# touch_board.net
KiCad netlist of a schematic drawn in EAGLE
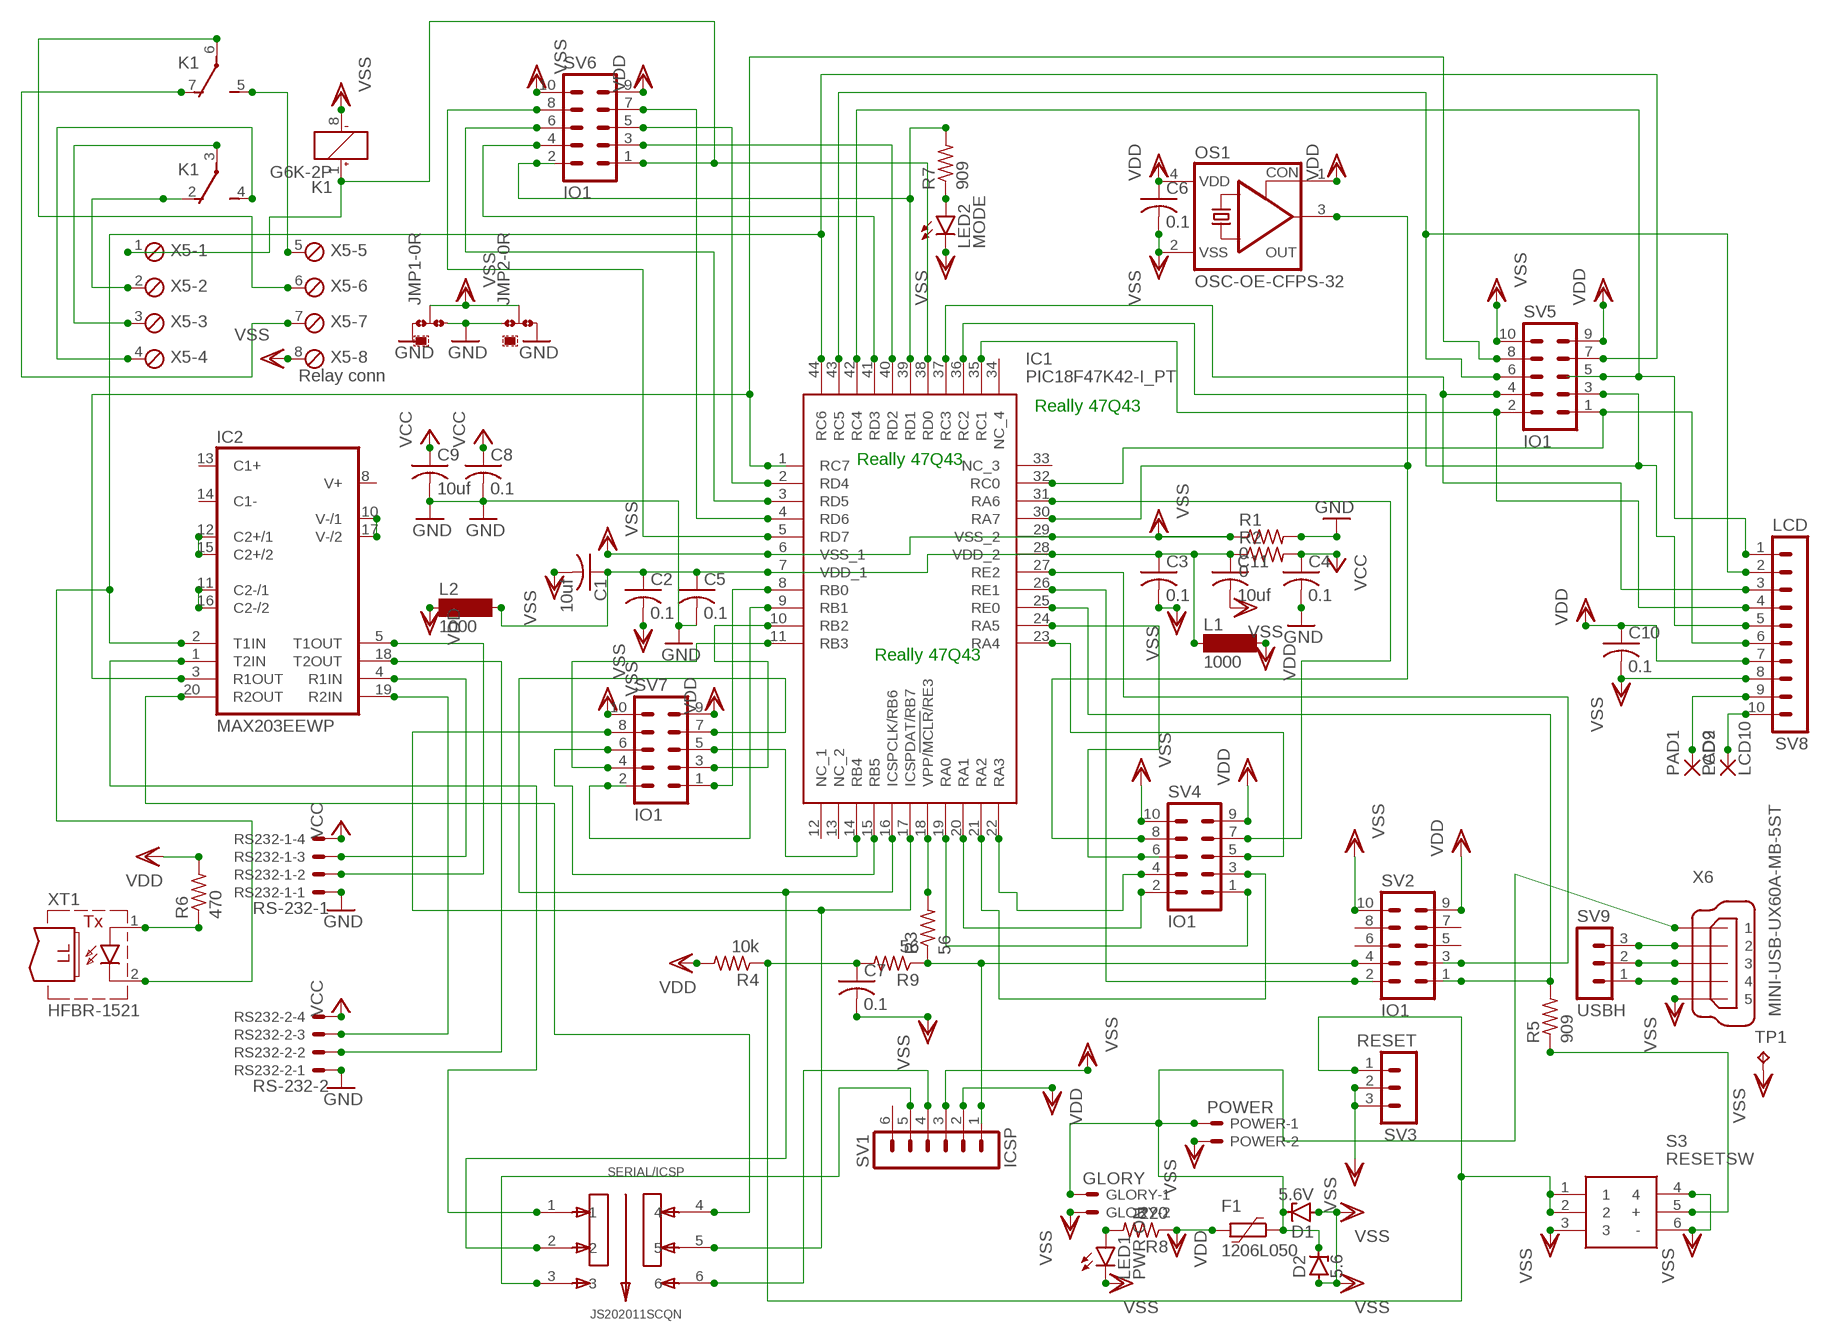
[diagram p0: schematic, sheet 1]

(export (version "E")
  (design (tool "Eeschema 10.0.6"))
  (components
    (comp (ref "C1")
      (value "10uf")
      (footprint "eagle-import:C0805")
      (libsource (lib "eagle-import") (part "C-USC0805"))
    )
    (comp (ref "C2")
      (value "0.1")
      (footprint "eagle-import:C0805")
      (libsource (lib "eagle-import") (part "C-USC0805"))
    )
    (comp (ref "C3")
      (value "0.1")
      (footprint "eagle-import:C0805")
      (libsource (lib "eagle-import") (part "C-USC0805"))
    )
    (comp (ref "C4")
      (value "0.1")
      (footprint "eagle-import:C0805")
      (libsource (lib "eagle-import") (part "C-USC0805"))
    )
    (comp (ref "C5")
      (value "0.1")
      (footprint "eagle-import:C0805")
      (libsource (lib "eagle-import") (part "C-USC0805"))
    )
    (comp (ref "C6")
      (value "0.1")
      (footprint "eagle-import:C0805")
      (libsource (lib "eagle-import") (part "C-USC0805"))
    )
    (comp (ref "C7")
      (value "0.1")
      (footprint "eagle-import:C0805")
      (libsource (lib "eagle-import") (part "C-USC0805"))
    )
    (comp (ref "C8")
      (value "0.1")
      (footprint "eagle-import:C0805")
      (libsource (lib "eagle-import") (part "C-USC0805"))
    )
    (comp (ref "C9")
      (value "10uf")
      (footprint "eagle-import:C0805")
      (libsource (lib "eagle-import") (part "C-USC0805"))
    )
    (comp (ref "C10")
      (value "0.1")
      (footprint "eagle-import:C0805")
      (libsource (lib "eagle-import") (part "C-USC0805"))
    )
    (comp (ref "C11")
      (value "10uf")
      (footprint "eagle-import:C0805")
      (libsource (lib "eagle-import") (part "C-USC0805"))
    )
    (comp (ref "D1")
      (value "5.6V")
      (footprint "eagle-import:ZDIO-7.5")
      (libsource (lib "eagle-import") (part "ZENER-DIODEZD-7.5"))
    )
    (comp (ref "D2")
      (value "5.6")
      (footprint "eagle-import:SMB")
      (libsource (lib "eagle-import") (part "ZENER-DIODESMB"))
    )
    (comp (ref "F1")
      (value "1206L050")
      (footprint "eagle-import:1206L")
      (fields (field (name "MF") "Littelfuse"))
      (libsource (lib "eagle-import") (part "?1206L050"))
    )
    (comp (ref "GLORY")
      (value "GLORY")
      (footprint "eagle-import:22-23-2021")
      (fields (field (name "MF") "MOLEX") (field (name "MPN") "22-23-2021"))
      (libsource (lib "eagle-import") (part "22-23-2021"))
    )
    (comp (ref "IC1")
      (value "PIC18F47K42-I_PT")
      (footprint "eagle-import:QFP80P1200X1200X120-44N")
      (fields
        (field (name "MANUFACTURER_PART_NUMBER") "PIC18F47K42-I/PT")
        (field (name "MOUSER_PART_NUMBER") "579-PIC18F47K42-I/PT")
      )
      (libsource (lib "eagle-import") (part "PIC18F47K42-I_PT"))
    )
    (comp (ref "IC2")
      (value "MAX203EEWP")
      (footprint "eagle-import:SO20L")
      (libsource (lib "eagle-import") (part "MAX203WPEE"))
    )
    (comp (ref "JMP1")
      (value "0R-JUMPA")
      (footprint "eagle-import:A0R-JMP")
      (libsource (lib "eagle-import") (part "0R-JUMPA"))
    )
    (comp (ref "JMP2")
      (value "0R-JUMPA")
      (footprint "eagle-import:A0R-JMP")
      (libsource (lib "eagle-import") (part "0R-JUMPA"))
    )
    (comp (ref "K1")
      (value "G6K-2P")
      (footprint "eagle-import:G6K-2P")
      (fields (field (name "MF") "OMRON COMPONENTS USA") (field (name "MPN") "G6K-2P DC3"))
      (libsource (lib "eagle-import") (part "G6K-2P"))
    )
    (comp (ref "L1")
      (value "1000")
      (footprint "eagle-import:SM-1206")
      (libsource (lib "eagle-import") (part "SM-1206"))
    )
    (comp (ref "L2")
      (value "1000")
      (footprint "eagle-import:SM-1206")
      (libsource (lib "eagle-import") (part "SM-1206"))
    )
    (comp (ref "LED1")
      (value "PWR ON")
      (footprint "eagle-import:CHIPLED_1206")
      (libsource (lib "eagle-import") (part "LEDCHIPLED_1206"))
    )
    (comp (ref "LED2")
      (value "MODE")
      (footprint "eagle-import:CHIPLED_1206")
      (libsource (lib "eagle-import") (part "LEDCHIPLED_1206"))
    )
    (comp (ref "OS1")
      (value "OSC-OE-CFPS-32")
      (footprint "eagle-import:7.2X5.2-4-PAD")
      (libsource (lib "eagle-import") (part "OSC-OE-CFPS-32"))
    )
    (comp (ref "PAD1")
      (value "LCD9")
      (footprint "eagle-import:SMD1,27-2,54")
      (libsource (lib "eagle-import") (part "SMD2"))
    )
    (comp (ref "PAD2")
      (value "LCD10")
      (footprint "eagle-import:SMD1,27-2,54")
      (libsource (lib "eagle-import") (part "SMD2"))
    )
    (comp (ref "POWER")
      (value "POWER")
      (footprint "eagle-import:22-23-2021")
      (fields (field (name "MF") "MOLEX") (field (name "MPN") "22-23-2021"))
      (libsource (lib "eagle-import") (part "22-23-2021"))
    )
    (comp (ref "R1")
      (value "0")
      (footprint "eagle-import:R0805")
      (libsource (lib "eagle-import") (part "R-US_R0805"))
    )
    (comp (ref "R2")
      (value "0")
      (footprint "eagle-import:R0805")
      (libsource (lib "eagle-import") (part "R-US_R0805"))
    )
    (comp (ref "R3")
      (value "56")
      (footprint "eagle-import:R0805")
      (libsource (lib "eagle-import") (part "R-US_R0805"))
    )
    (comp (ref "R4")
      (value "10k")
      (footprint "eagle-import:R0805")
      (libsource (lib "eagle-import") (part "R-US_R0805"))
    )
    (comp (ref "R5")
      (value "909")
      (footprint "eagle-import:R0805")
      (libsource (lib "eagle-import") (part "R-US_R0805"))
    )
    (comp (ref "R6")
      (value "470")
      (footprint "eagle-import:R0805")
      (libsource (lib "eagle-import") (part "R-US_R0805"))
    )
    (comp (ref "R7")
      (value "909")
      (footprint "eagle-import:R0805")
      (libsource (lib "eagle-import") (part "R-US_R0805"))
    )
    (comp (ref "R8")
      (value "220")
      (footprint "eagle-import:R0805")
      (libsource (lib "eagle-import") (part "R-US_R0805"))
    )
    (comp (ref "R9")
      (value "56")
      (footprint "eagle-import:R0805")
      (libsource (lib "eagle-import") (part "R-US_R0805"))
    )
    (comp (ref "RS232-1")
      (value "RS-232-1")
      (footprint "eagle-import:22-23-2041")
      (fields (field (name "MF") "MOLEX") (field (name "MPN") "22-23-2041"))
      (libsource (lib "eagle-import") (part "22-23-2041"))
    )
    (comp (ref "RS232-2")
      (value "RS-232-2")
      (footprint "eagle-import:22-23-2041")
      (fields (field (name "MF") "MOLEX") (field (name "MPN") "22-23-2041"))
      (libsource (lib "eagle-import") (part "22-23-2041"))
    )
    (comp (ref "S3")
      (value "RESETSW")
      (footprint "eagle-import:B3W-9_1-LED")
      (fields
        (field (name "MANUFACTURER_PART_NUMBER") "B3W-9000-Y1N")
        (field (name "MOUSER_PART_NUMBER") "653-B3W-9000-Y1N")
        (field (name "RS_PART_NUMBER") "0492777P")
      )
      (libsource (lib "eagle-import") (part "B3W-9000-Y1N"))
    )
    (comp (ref "SERIAL/ICSP")
      (value "JS202011SCQN")
      (footprint "eagle-import:SW_JS202011SCQN")
      (fields (field (name "MF") "C&K"))
      (libsource (lib "eagle-import") (part "JS202011SCQN"))
    )
    (comp (ref "SV1")
      (value "ICSP")
      (footprint "eagle-import:MA06-1")
      (libsource (lib "eagle-import") (part "MA06-1"))
    )
    (comp (ref "SV2")
      (value "IO1")
      (footprint "eagle-import:MA05-2")
      (libsource (lib "eagle-import") (part "MA05-2"))
    )
    (comp (ref "SV3")
      (value "RESET")
      (footprint "eagle-import:MA03-1")
      (libsource (lib "eagle-import") (part "MA03-1"))
    )
    (comp (ref "SV4")
      (value "IO1")
      (footprint "eagle-import:MA05-2")
      (libsource (lib "eagle-import") (part "MA05-2"))
    )
    (comp (ref "SV5")
      (value "IO1")
      (footprint "eagle-import:MA05-2")
      (libsource (lib "eagle-import") (part "MA05-2"))
    )
    (comp (ref "SV6")
      (value "IO1")
      (footprint "eagle-import:MA05-2")
      (libsource (lib "eagle-import") (part "MA05-2"))
    )
    (comp (ref "SV7")
      (value "IO1")
      (footprint "eagle-import:MA05-2")
      (libsource (lib "eagle-import") (part "MA05-2"))
    )
    (comp (ref "SV8")
      (value "LCD")
      (footprint "eagle-import:MA10-1")
      (libsource (lib "eagle-import") (part "MA10-1"))
    )
    (comp (ref "SV9")
      (value "USBH")
      (footprint "eagle-import:MA03-1")
      (libsource (lib "eagle-import") (part "MA03-1"))
    )
    (comp (ref "TP1")
      (value "TPB1,27")
      (footprint "eagle-import:B1,27")
      (libsource (lib "eagle-import") (part "TPB1,27"))
    )
    (comp (ref "X5")
      (value "Relay conn")
      (footprint "eagle-import:8POL254")
      (libsource (lib "eagle-import") (part "MPT8"))
    )
    (comp (ref "X6")
      (value "MINI-USB-UX60A-MB-5ST")
      (footprint "eagle-import:UX60A-MB-5ST")
      (libsource (lib "eagle-import") (part "MINI-USB-UX60A-MB-5ST"))
    )
    (comp (ref "XT1")
      (value "HFBR-1521")
      (footprint "eagle-import:HFBR-15X3")
      (fields (field (name "MF") "AGILENT TECHNOLOGIES"))
      (libsource (lib "eagle-import") (part "HFBR-1521"))
    )
  )
  (nets
    (net (code "1") (name "GND") (class "Default")
      (node (ref "C4") (pin "2") (pinfunction "2_2") (pintype "passive"))
      (node (ref "C5") (pin "2") (pinfunction "2_2") (pintype "passive"))
      (node (ref "C8") (pin "2") (pinfunction "2_2") (pintype "passive"))
      (node (ref "C9") (pin "2") (pinfunction "2_2") (pintype "passive"))
      (node (ref "JMP1") (pin "1") (pinfunction "1_1") (pintype "passive"))
      (node (ref "JMP1") (pin "3") (pinfunction "3_3") (pintype "passive"))
      (node (ref "JMP2") (pin "1") (pinfunction "1_1") (pintype "passive"))
      (node (ref "JMP2") (pin "3") (pinfunction "3_3") (pintype "passive"))
      (node (ref "R1") (pin "2") (pinfunction "2_2") (pintype "passive"))
      (node (ref "RS232-1") (pin "1") (pinfunction "S_1") (pintype "passive"))
      (node (ref "RS232-2") (pin "1") (pinfunction "S_1") (pintype "passive"))
    )
    (net (code "2") (name "Net-(C7-Pad1)") (class "Default")
      (node (ref "C7") (pin "1") (pinfunction "1_1") (pintype "passive"))
      (node (ref "R4") (pin "1") (pinfunction "1_1") (pintype "passive"))
      (node (ref "R9") (pin "2") (pinfunction "2_2") (pintype "passive"))
      (node (ref "S3") (pin "1") (pinfunction "1_1") (pintype "bidirectional"))
      (node (ref "S3") (pin "2") (pinfunction "2_2") (pintype "bidirectional"))
      (node (ref "SV3") (pin "1") (pinfunction "1_1") (pintype "passive"))
    )
    (net (code "3") (name "Net-(GLORYA-S)") (class "Default")
      (node (ref "D1") (pin "C") (pinfunction "C_C") (pintype "passive"))
      (node (ref "D2") (pin "C") (pinfunction "C_C") (pintype "passive"))
      (node (ref "F1") (pin "1") (pinfunction "1_1") (pintype "passive"))
      (node (ref "GLORY") (pin "1") (pinfunction "S_1") (pintype "passive"))
      (node (ref "POWER") (pin "1") (pinfunction "S_1") (pintype "passive"))
      (node (ref "X6") (pin "1") (pinfunction "1_1") (pintype "input"))
    )
    (net (code "4") (name "Net-(IC1-ICSPCLK{slash}RB6)") (class "Default")
      (node (ref "IC1") (pin "16") (pinfunction "ICSPCLK/RB6_16") (pintype "bidirectional"))
      (node (ref "SERIAL/ICSP") (pin "2") (pinfunction "2_2") (pintype "passive"))
      (node (ref "SV7") (pin "7") (pinfunction "7_7") (pintype "passive"))
    )
    (net (code "5") (name "Net-(IC1-ICSPDAT{slash}RB7)") (class "Default")
      (node (ref "IC1") (pin "17") (pinfunction "ICSPDAT/RB7_17") (pintype "bidirectional"))
      (node (ref "SERIAL/ICSP") (pin "5") (pinfunction "5_5") (pintype "passive"))
      (node (ref "SV7") (pin "8") (pinfunction "8_8") (pintype "passive"))
    )
    (net (code "6") (name "Net-(IC1-RA0)") (class "Default")
      (node (ref "IC1") (pin "19") (pinfunction "RA0_19") (pintype "bidirectional"))
      (node (ref "SV4") (pin "1") (pinfunction "1_1") (pintype "passive"))
    )
    (net (code "7") (name "Net-(IC1-RA1)") (class "Default")
      (node (ref "IC1") (pin "20") (pinfunction "RA1_20") (pintype "bidirectional"))
      (node (ref "SV4") (pin "2") (pinfunction "2_2") (pintype "passive"))
    )
    (net (code "8") (name "Net-(IC1-RA2)") (class "Default")
      (node (ref "IC1") (pin "21") (pinfunction "RA2_21") (pintype "bidirectional"))
      (node (ref "SV4") (pin "3") (pinfunction "3_3") (pintype "passive"))
    )
    (net (code "9") (name "Net-(IC1-RA3)") (class "Default")
      (node (ref "IC1") (pin "22") (pinfunction "RA3_22") (pintype "bidirectional"))
      (node (ref "SV4") (pin "4") (pinfunction "4_4") (pintype "passive"))
    )
    (net (code "10") (name "Net-(IC1-RA4)") (class "Default")
      (node (ref "IC1") (pin "23") (pinfunction "RA4_23") (pintype "bidirectional"))
      (node (ref "SV4") (pin "5") (pinfunction "5_5") (pintype "passive"))
    )
    (net (code "11") (name "Net-(IC1-RA5)") (class "Default")
      (node (ref "IC1") (pin "24") (pinfunction "RA5_24") (pintype "bidirectional"))
      (node (ref "SV4") (pin "6") (pinfunction "6_6") (pintype "passive"))
    )
    (net (code "12") (name "Net-(IC1-RA6)") (class "Default")
      (node (ref "IC1") (pin "31") (pinfunction "RA6_31") (pintype "bidirectional"))
      (node (ref "SV4") (pin "7") (pinfunction "7_7") (pintype "passive"))
    )
    (net (code "13") (name "Net-(IC1-RA7)") (class "Default")
      (node (ref "IC1") (pin "30") (pinfunction "RA7_30") (pintype "bidirectional"))
      (node (ref "OS1") (pin "3") (pinfunction "OUT_3") (pintype "output"))
      (node (ref "SV4") (pin "8") (pinfunction "8_8") (pintype "passive"))
    )
    (net (code "14") (name "Net-(IC1-RB0)") (class "Default")
      (node (ref "IC1") (pin "8") (pinfunction "RB0_8") (pintype "bidirectional"))
      (node (ref "SV7") (pin "1") (pinfunction "1_1") (pintype "passive"))
    )
    (net (code "15") (name "Net-(IC1-RB1)") (class "Default")
      (node (ref "IC1") (pin "9") (pinfunction "RB1_9") (pintype "bidirectional"))
      (node (ref "SV7") (pin "2") (pinfunction "2_2") (pintype "passive"))
    )
    (net (code "16") (name "Net-(IC1-RB2)") (class "Default")
      (node (ref "IC1") (pin "10") (pinfunction "RB2_10") (pintype "bidirectional"))
      (node (ref "SV7") (pin "3") (pinfunction "3_3") (pintype "passive"))
    )
    (net (code "17") (name "Net-(IC1-RB3)") (class "Default")
      (node (ref "IC1") (pin "11") (pinfunction "RB3_11") (pintype "bidirectional"))
      (node (ref "SV7") (pin "4") (pinfunction "4_4") (pintype "passive"))
    )
    (net (code "18") (name "Net-(IC1-RB4)") (class "Default")
      (node (ref "IC1") (pin "14") (pinfunction "RB4_14") (pintype "bidirectional"))
      (node (ref "SV7") (pin "5") (pinfunction "5_5") (pintype "passive"))
    )
    (net (code "19") (name "Net-(IC1-RB5)") (class "Default")
      (node (ref "IC1") (pin "15") (pinfunction "RB5_15") (pintype "bidirectional"))
      (node (ref "SV7") (pin "6") (pinfunction "6_6") (pintype "passive"))
    )
    (net (code "20") (name "Net-(IC1-RC0)") (class "Default")
      (node (ref "IC1") (pin "32") (pinfunction "RC0_32") (pintype "bidirectional"))
      (node (ref "SV5") (pin "1") (pinfunction "1_1") (pintype "passive"))
      (node (ref "SV8") (pin "6") (pinfunction "6_6") (pintype "passive"))
    )
    (net (code "21") (name "Net-(IC1-RC1)") (class "Default")
      (node (ref "IC1") (pin "35") (pinfunction "RC1_35") (pintype "bidirectional"))
      (node (ref "SV5") (pin "2") (pinfunction "2_2") (pintype "passive"))
      (node (ref "SV8") (pin "4") (pinfunction "4_4") (pintype "passive"))
    )
    (net (code "22") (name "Net-(IC1-RC2)") (class "Default")
      (node (ref "IC1") (pin "36") (pinfunction "RC2_36") (pintype "bidirectional"))
      (node (ref "SV5") (pin "3") (pinfunction "3_3") (pintype "passive"))
      (node (ref "SV8") (pin "5") (pinfunction "5_5") (pintype "passive"))
    )
    (net (code "23") (name "Net-(IC1-RC3)") (class "Default")
      (node (ref "IC1") (pin "37") (pinfunction "RC3_37") (pintype "bidirectional"))
      (node (ref "SV5") (pin "4") (pinfunction "4_4") (pintype "passive"))
      (node (ref "SV8") (pin "3") (pinfunction "3_3") (pintype "passive"))
    )
    (net (code "24") (name "Net-(IC1-RC4)") (class "Default")
      (node (ref "IC1") (pin "42") (pinfunction "RC4_42") (pintype "bidirectional"))
      (node (ref "SV5") (pin "5") (pinfunction "5_5") (pintype "passive"))
      (node (ref "SV8") (pin "1") (pinfunction "1_1") (pintype "passive"))
    )
    (net (code "25") (name "Net-(IC1-RC5)") (class "Default")
      (node (ref "IC1") (pin "43") (pinfunction "RC5_43") (pintype "bidirectional"))
      (node (ref "SV5") (pin "6") (pinfunction "6_6") (pintype "passive"))
      (node (ref "SV8") (pin "2") (pinfunction "2_2") (pintype "passive"))
    )
    (net (code "26") (name "Net-(IC1-RC6)") (class "Default")
      (node (ref "IC1") (pin "44") (pinfunction "RC6_44") (pintype "bidirectional"))
      (node (ref "IC2") (pin "2") (pinfunction "T1IN_2") (pintype "input"))
      (node (ref "SV5") (pin "7") (pinfunction "7_7") (pintype "passive"))
      (node (ref "XT1") (pin "2") (pinfunction "C_2") (pintype "passive"))
    )
    (net (code "27") (name "Net-(IC1-RC7)") (class "Default")
      (node (ref "IC1") (pin "1") (pinfunction "RC7_1") (pintype "bidirectional"))
      (node (ref "IC2") (pin "3") (pinfunction "R1OUT_3") (pintype "output"))
      (node (ref "SV5") (pin "8") (pinfunction "8_8") (pintype "passive"))
    )
    (net (code "28") (name "Net-(IC1-RD0)") (class "Default")
      (node (ref "IC1") (pin "38") (pinfunction "RD0_38") (pintype "bidirectional"))
      (node (ref "K1") (pin "1") (pinfunction "+_1") (pintype "passive"))
      (node (ref "SV6") (pin "1") (pinfunction "1_1") (pintype "passive"))
      (node (ref "X5") (pin "1") (pinfunction "1_1") (pintype "passive"))
    )
    (net (code "29") (name "Net-(IC1-RD1)") (class "Default")
      (node (ref "IC1") (pin "39") (pinfunction "RD1_39") (pintype "bidirectional"))
      (node (ref "R7") (pin "2") (pinfunction "2_2") (pintype "passive"))
      (node (ref "SV6") (pin "2") (pinfunction "2_2") (pintype "passive"))
    )
    (net (code "30") (name "Net-(IC1-RD2)") (class "Default")
      (node (ref "IC1") (pin "40") (pinfunction "RD2_40") (pintype "bidirectional"))
      (node (ref "SV6") (pin "3") (pinfunction "3_3") (pintype "passive"))
    )
    (net (code "31") (name "Net-(IC1-RD3)") (class "Default")
      (node (ref "IC1") (pin "41") (pinfunction "RD3_41") (pintype "bidirectional"))
      (node (ref "SV6") (pin "4") (pinfunction "4_4") (pintype "passive"))
    )
    (net (code "32") (name "Net-(IC1-RD4)") (class "Default")
      (node (ref "IC1") (pin "2") (pinfunction "RD4_2") (pintype "bidirectional"))
      (node (ref "SV6") (pin "5") (pinfunction "5_5") (pintype "passive"))
    )
    (net (code "33") (name "Net-(IC1-RD5)") (class "Default")
      (node (ref "IC1") (pin "3") (pinfunction "RD5_3") (pintype "bidirectional"))
      (node (ref "SV6") (pin "6") (pinfunction "6_6") (pintype "passive"))
    )
    (net (code "34") (name "Net-(IC1-RD6)") (class "Default")
      (node (ref "IC1") (pin "4") (pinfunction "RD6_4") (pintype "bidirectional"))
      (node (ref "SV6") (pin "7") (pinfunction "7_7") (pintype "passive"))
    )
    (net (code "35") (name "Net-(IC1-RD7)") (class "Default")
      (node (ref "IC1") (pin "5") (pinfunction "RD7_5") (pintype "bidirectional"))
      (node (ref "SV6") (pin "8") (pinfunction "8_8") (pintype "passive"))
    )
    (net (code "36") (name "Net-(IC1-RE0)") (class "Default")
      (node (ref "IC1") (pin "25") (pinfunction "RE0_25") (pintype "bidirectional"))
      (node (ref "R5") (pin "2") (pinfunction "2_2") (pintype "passive"))
      (node (ref "SV2") (pin "1") (pinfunction "1_1") (pintype "passive"))
    )
    (net (code "37") (name "Net-(IC1-RE1)") (class "Default")
      (node (ref "IC1") (pin "26") (pinfunction "RE1_26") (pintype "bidirectional"))
      (node (ref "SV2") (pin "2") (pinfunction "2_2") (pintype "passive"))
    )
    (net (code "38") (name "Net-(IC1-RE2)") (class "Default")
      (node (ref "IC1") (pin "27") (pinfunction "RE2_27") (pintype "bidirectional"))
      (node (ref "SV2") (pin "3") (pinfunction "3_3") (pintype "passive"))
    )
    (net (code "39") (name "Net-(IC1-VDD_1)") (class "Default")
      (node (ref "C1") (pin "1") (pinfunction "1_1") (pintype "passive"))
      (node (ref "C11") (pin "1") (pinfunction "1_1") (pintype "passive"))
      (node (ref "C2") (pin "1") (pinfunction "1_1") (pintype "passive"))
      (node (ref "C3") (pin "1") (pinfunction "1_1") (pintype "passive"))
      (node (ref "C5") (pin "1") (pinfunction "1_1") (pintype "passive"))
      (node (ref "IC1") (pin "28") (pinfunction "VDD_2_28") (pintype "bidirectional"))
      (node (ref "IC1") (pin "7") (pinfunction "VDD_1_7") (pintype "bidirectional"))
      (node (ref "L1") (pin "1") (pinfunction "1_1") (pintype "passive"))
      (node (ref "L2") (pin "2") (pinfunction "2_2") (pintype "passive"))
      (node (ref "R2") (pin "1") (pinfunction "1_1") (pintype "passive"))
    )
    (net (code "40") (name "Net-(IC1-VPP{slash}~{MCLR}{slash}RE3)") (class "Default")
      (node (ref "IC1") (pin "18") (pinfunction "VPP/~{MCLR}/RE3_18") (pintype "bidirectional"))
      (node (ref "R3") (pin "2") (pinfunction "2_2") (pintype "passive"))
    )
    (net (code "41") (name "Net-(IC2A-C2+{slash}1)") (class "Default")
      (node (ref "IC2") (pin "12") (pinfunction "C2+/1_12") (pintype "passive"))
      (node (ref "IC2") (pin "15") (pinfunction "C2+/2_15") (pintype "passive"))
    )
    (net (code "42") (name "Net-(IC2A-C2-{slash}1)") (class "Default")
      (node (ref "IC2") (pin "11") (pinfunction "C2-/1_11") (pintype "passive"))
      (node (ref "IC2") (pin "16") (pinfunction "C2-/2_16") (pintype "passive"))
    )
    (net (code "43") (name "Net-(IC2A-R1IN)") (class "Default")
      (node (ref "IC2") (pin "4") (pinfunction "R1IN_4") (pintype "input"))
      (node (ref "RS232-1") (pin "3") (pinfunction "S_3") (pintype "passive"))
    )
    (net (code "44") (name "Net-(IC2A-R2IN)") (class "Default")
      (node (ref "IC2") (pin "19") (pinfunction "R2IN_19") (pintype "input"))
      (node (ref "RS232-2") (pin "3") (pinfunction "S_3") (pintype "passive"))
    )
    (net (code "45") (name "Net-(IC2A-R2OUT)") (class "Default")
      (node (ref "IC2") (pin "20") (pinfunction "R2OUT_20") (pintype "output"))
      (node (ref "SERIAL/ICSP") (pin "4") (pinfunction "4_4") (pintype "passive"))
    )
    (net (code "46") (name "Net-(IC2A-T1OUT)") (class "Default")
      (node (ref "IC2") (pin "5") (pinfunction "T1OUT_5") (pintype "output"))
      (node (ref "RS232-1") (pin "2") (pinfunction "S_2") (pintype "passive"))
    )
    (net (code "47") (name "Net-(IC2A-T2IN)") (class "Default")
      (node (ref "IC2") (pin "1") (pinfunction "T2IN_1") (pintype "input"))
      (node (ref "SERIAL/ICSP") (pin "1") (pinfunction "1_1") (pintype "passive"))
    )
    (net (code "48") (name "Net-(IC2A-T2OUT)") (class "Default")
      (node (ref "IC2") (pin "18") (pinfunction "T2OUT_18") (pintype "output"))
      (node (ref "RS232-2") (pin "2") (pinfunction "S_2") (pintype "passive"))
    )
    (net (code "49") (name "Net-(IC2A-V-{slash}1)") (class "Default")
      (node (ref "IC2") (pin "10") (pinfunction "V-/1_10") (pintype "passive"))
      (node (ref "IC2") (pin "17") (pinfunction "V-/2_17") (pintype "passive"))
    )
    (net (code "50") (name "Net-(K1B-O)") (class "Default")
      (node (ref "K1") (pin "2") (pinfunction "O_2") (pintype "passive"))
      (node (ref "X5") (pin "2") (pinfunction "1_2") (pintype "passive"))
    )
    (net (code "51") (name "Net-(K1B-P)") (class "Default")
      (node (ref "K1") (pin "3") (pinfunction "P_3") (pintype "passive"))
      (node (ref "X5") (pin "3") (pinfunction "1_3") (pintype "passive"))
    )
    (net (code "52") (name "Net-(K1B-S)") (class "Default")
      (node (ref "K1") (pin "4") (pinfunction "S_4") (pintype "passive"))
      (node (ref "X5") (pin "4") (pinfunction "1_4") (pintype "passive"))
    )
    (net (code "53") (name "Net-(K1C-O)") (class "Default")
      (node (ref "K1") (pin "7") (pinfunction "O_7") (pintype "passive"))
      (node (ref "X5") (pin "7") (pinfunction "1_7") (pintype "passive"))
    )
    (net (code "54") (name "Net-(K1C-P)") (class "Default")
      (node (ref "K1") (pin "6") (pinfunction "P_6") (pintype "passive"))
      (node (ref "X5") (pin "6") (pinfunction "1_6") (pintype "passive"))
    )
    (net (code "55") (name "Net-(K1C-S)") (class "Default")
      (node (ref "K1") (pin "5") (pinfunction "S_5") (pintype "passive"))
      (node (ref "X5") (pin "5") (pinfunction "1_5") (pintype "passive"))
    )
    (net (code "56") (name "Net-(LED1-PadA)") (class "Default")
      (node (ref "LED1") (pin "A") (pinfunction "A_A") (pintype "passive"))
      (node (ref "R8") (pin "2") (pinfunction "2_2") (pintype "passive"))
    )
    (net (code "57") (name "Net-(LED2-PadA)") (class "Default")
      (node (ref "LED2") (pin "A") (pinfunction "A_A") (pintype "passive"))
      (node (ref "R7") (pin "1") (pinfunction "1_1") (pintype "passive"))
    )
    (net (code "58") (name "Net-(PAD1-P)") (class "Default")
      (node (ref "PAD1") (pin "1") (pinfunction "P_1") (pintype "passive"))
      (node (ref "SV8") (pin "9") (pinfunction "9_9") (pintype "passive"))
    )
    (net (code "59") (name "Net-(PAD2-P)") (class "Default")
      (node (ref "PAD2") (pin "1") (pinfunction "P_1") (pintype "passive"))
      (node (ref "SV8") (pin "10") (pinfunction "10_10") (pintype "passive"))
    )
    (net (code "60") (name "Net-(R3-Pad1)") (class "Default")
      (node (ref "R3") (pin "1") (pinfunction "1_1") (pintype "passive"))
      (node (ref "R9") (pin "1") (pinfunction "1_1") (pintype "passive"))
      (node (ref "SV1") (pin "1") (pinfunction "1_1") (pintype "passive"))
      (node (ref "SV2") (pin "4") (pinfunction "4_4") (pintype "passive"))
    )
    (net (code "61") (name "Net-(S3-+)") (class "Default")
      (node (ref "R5") (pin "1") (pinfunction "1_1") (pintype "passive"))
      (node (ref "S3") (pin "5") (pinfunction "+_5") (pintype "bidirectional"))
    )
    (net (code "62") (name "Net-(SERIAL/ICSP-Pad3)") (class "Default")
      (node (ref "SERIAL/ICSP") (pin "3") (pinfunction "3_3") (pintype "passive"))
      (node (ref "SV1") (pin "5") (pinfunction "5_5") (pintype "passive"))
    )
    (net (code "63") (name "Net-(SERIAL/ICSP-Pad6)") (class "Default")
      (node (ref "SERIAL/ICSP") (pin "6") (pinfunction "6_6") (pintype "passive"))
      (node (ref "SV1") (pin "4") (pinfunction "4_4") (pintype "passive"))
    )
    (net (code "64") (name "Net-(SV9-Pad1)") (class "Default")
      (node (ref "SV9") (pin "1") (pinfunction "1_1") (pintype "passive"))
      (node (ref "X6") (pin "4") (pinfunction "4_4") (pintype "input"))
    )
    (net (code "65") (name "Net-(SV9-Pad2)") (class "Default")
      (node (ref "SV9") (pin "2") (pinfunction "2_2") (pintype "passive"))
      (node (ref "X6") (pin "3") (pinfunction "3_3") (pintype "input"))
    )
    (net (code "66") (name "Net-(SV9-Pad3)") (class "Default")
      (node (ref "SV9") (pin "3") (pinfunction "3_3") (pintype "passive"))
      (node (ref "X6") (pin "2") (pinfunction "2_2") (pintype "input"))
    )
    (net (code "67") (name "Net-(XT1-A)") (class "Default")
      (node (ref "R6") (pin "1") (pinfunction "1_1") (pintype "passive"))
      (node (ref "XT1") (pin "1") (pinfunction "A_1") (pintype "passive"))
    )
    (net (code "68") (name "VCC") (class "Default")
      (node (ref "C4") (pin "1") (pinfunction "1_1") (pintype "passive"))
      (node (ref "C8") (pin "1") (pinfunction "1_1") (pintype "passive"))
      (node (ref "C9") (pin "1") (pinfunction "1_1") (pintype "passive"))
      (node (ref "R2") (pin "2") (pinfunction "2_2") (pintype "passive"))
      (node (ref "RS232-1") (pin "4") (pinfunction "S_4") (pintype "passive"))
      (node (ref "RS232-2") (pin "4") (pinfunction "S_4") (pintype "passive"))
    )
    (net (code "69") (name "VDD") (class "Default")
      (node (ref "C10") (pin "1") (pinfunction "1_1") (pintype "passive"))
      (node (ref "C6") (pin "1") (pinfunction "1_1") (pintype "passive"))
      (node (ref "F1") (pin "2") (pinfunction "2_2") (pintype "passive"))
      (node (ref "L1") (pin "2") (pinfunction "2_2") (pintype "passive"))
      (node (ref "L2") (pin "1") (pinfunction "1_1") (pintype "passive"))
      (node (ref "OS1") (pin "1") (pinfunction "CON_1") (pintype "input"))
      (node (ref "OS1") (pin "4") (pinfunction "VDD_4") (pintype "power_in"))
      (node (ref "R4") (pin "2") (pinfunction "2_2") (pintype "passive"))
      (node (ref "R6") (pin "2") (pinfunction "2_2") (pintype "passive"))
      (node (ref "R8") (pin "1") (pinfunction "1_1") (pintype "passive"))
      (node (ref "SV1") (pin "2") (pinfunction "2_2") (pintype "passive"))
      (node (ref "SV2") (pin "9") (pinfunction "9_9") (pintype "passive"))
      (node (ref "SV4") (pin "9") (pinfunction "9_9") (pintype "passive"))
      (node (ref "SV5") (pin "9") (pinfunction "9_9") (pintype "passive"))
      (node (ref "SV6") (pin "9") (pinfunction "9_9") (pintype "passive"))
      (node (ref "SV7") (pin "9") (pinfunction "9_9") (pintype "passive"))
      (node (ref "SV8") (pin "7") (pinfunction "7_7") (pintype "passive"))
    )
    (net (code "70") (name "VSS") (class "Default")
      (node (ref "C1") (pin "2") (pinfunction "2_2") (pintype "passive"))
      (node (ref "C10") (pin "2") (pinfunction "2_2") (pintype "passive"))
      (node (ref "C11") (pin "2") (pinfunction "2_2") (pintype "passive"))
      (node (ref "C2") (pin "2") (pinfunction "2_2") (pintype "passive"))
      (node (ref "C3") (pin "2") (pinfunction "2_2") (pintype "passive"))
      (node (ref "C6") (pin "2") (pinfunction "2_2") (pintype "passive"))
      (node (ref "C7") (pin "2") (pinfunction "2_2") (pintype "passive"))
      (node (ref "D1") (pin "A") (pinfunction "A_A") (pintype "passive"))
      (node (ref "D2") (pin "A") (pinfunction "A_A") (pintype "passive"))
      (node (ref "GLORY") (pin "2") (pinfunction "S_2") (pintype "passive"))
      (node (ref "IC1") (pin "29") (pinfunction "VSS_2_29") (pintype "bidirectional"))
      (node (ref "IC1") (pin "6") (pinfunction "VSS_1_6") (pintype "bidirectional"))
      (node (ref "JMP1") (pin "2") (pinfunction "2_2") (pintype "passive"))
      (node (ref "JMP2") (pin "2") (pinfunction "2_2") (pintype "passive"))
      (node (ref "K1") (pin "8") (pinfunction "-_8") (pintype "passive"))
      (node (ref "LED1") (pin "C") (pinfunction "C_C") (pintype "passive"))
      (node (ref "LED2") (pin "C") (pinfunction "C_C") (pintype "passive"))
      (node (ref "OS1") (pin "2") (pinfunction "VSS_2") (pintype "power_in"))
      (node (ref "POWER") (pin "2") (pinfunction "S_2") (pintype "passive"))
      (node (ref "R1") (pin "1") (pinfunction "1_1") (pintype "passive"))
      (node (ref "S3") (pin "3") (pinfunction "3_3") (pintype "bidirectional"))
      (node (ref "S3") (pin "4") (pinfunction "4_4") (pintype "bidirectional"))
      (node (ref "S3") (pin "6") (pinfunction "-_6") (pintype "bidirectional"))
      (node (ref "SV1") (pin "3") (pinfunction "3_3") (pintype "passive"))
      (node (ref "SV2") (pin "10") (pinfunction "10_10") (pintype "passive"))
      (node (ref "SV3") (pin "2") (pinfunction "2_2") (pintype "passive"))
      (node (ref "SV3") (pin "3") (pinfunction "3_3") (pintype "passive"))
      (node (ref "SV4") (pin "10") (pinfunction "10_10") (pintype "passive"))
      (node (ref "SV5") (pin "10") (pinfunction "10_10") (pintype "passive"))
      (node (ref "SV6") (pin "10") (pinfunction "10_10") (pintype "passive"))
      (node (ref "SV7") (pin "10") (pinfunction "10_10") (pintype "passive"))
      (node (ref "SV8") (pin "8") (pinfunction "8_8") (pintype "passive"))
      (node (ref "TP1") (pin "TP") (pinfunction "TP_TP") (pintype "input"))
      (node (ref "X5") (pin "8") (pinfunction "1_8") (pintype "passive"))
      (node (ref "X6") (pin "5") (pinfunction "5_5") (pintype "input"))
    )
    (net (code "71") (name "unconnected-(IC1-NC_1-Pad12)") (class "Default")
      (node (ref "IC1") (pin "12") (pinfunction "NC_1_12") (pintype "bidirectional"))
    )
    (net (code "72") (name "unconnected-(IC1-NC_2-Pad13)") (class "Default")
      (node (ref "IC1") (pin "13") (pinfunction "NC_2_13") (pintype "bidirectional"))
    )
    (net (code "73") (name "unconnected-(IC1-NC_3-Pad33)") (class "Default")
      (node (ref "IC1") (pin "33") (pinfunction "NC_3_33") (pintype "bidirectional"))
    )
    (net (code "74") (name "unconnected-(IC1-NC_4-Pad34)") (class "Default")
      (node (ref "IC1") (pin "34") (pinfunction "NC_4_34") (pintype "bidirectional"))
    )
    (net (code "75") (name "unconnected-(IC2A-C1+-Pad13)") (class "Default")
      (node (ref "IC2") (pin "13") (pinfunction "C1+_13") (pintype "passive"))
    )
    (net (code "76") (name "unconnected-(IC2A-C1--Pad14)") (class "Default")
      (node (ref "IC2") (pin "14") (pinfunction "C1-_14") (pintype "passive"))
    )
    (net (code "77") (name "unconnected-(IC2A-V+-Pad8)") (class "Default")
      (node (ref "IC2") (pin "8") (pinfunction "V+_8") (pintype "passive"))
    )
    (net (code "78") (name "unconnected-(SV1-Pad6)") (class "Default")
      (node (ref "SV1") (pin "6") (pinfunction "6_6") (pintype "passive"))
    )
    (net (code "79") (name "unconnected-(SV2-Pad5)") (class "Default")
      (node (ref "SV2") (pin "5") (pinfunction "5_5") (pintype "passive"))
    )
    (net (code "80") (name "unconnected-(SV2-Pad6)") (class "Default")
      (node (ref "SV2") (pin "6") (pinfunction "6_6") (pintype "passive"))
    )
    (net (code "81") (name "unconnected-(SV2-Pad7)") (class "Default")
      (node (ref "SV2") (pin "7") (pinfunction "7_7") (pintype "passive"))
    )
    (net (code "82") (name "unconnected-(SV2-Pad8)") (class "Default")
      (node (ref "SV2") (pin "8") (pinfunction "8_8") (pintype "passive"))
    )
  )
)
